# Sheet1.net
KiCad netlist of a schematic drawn in Altium Designer
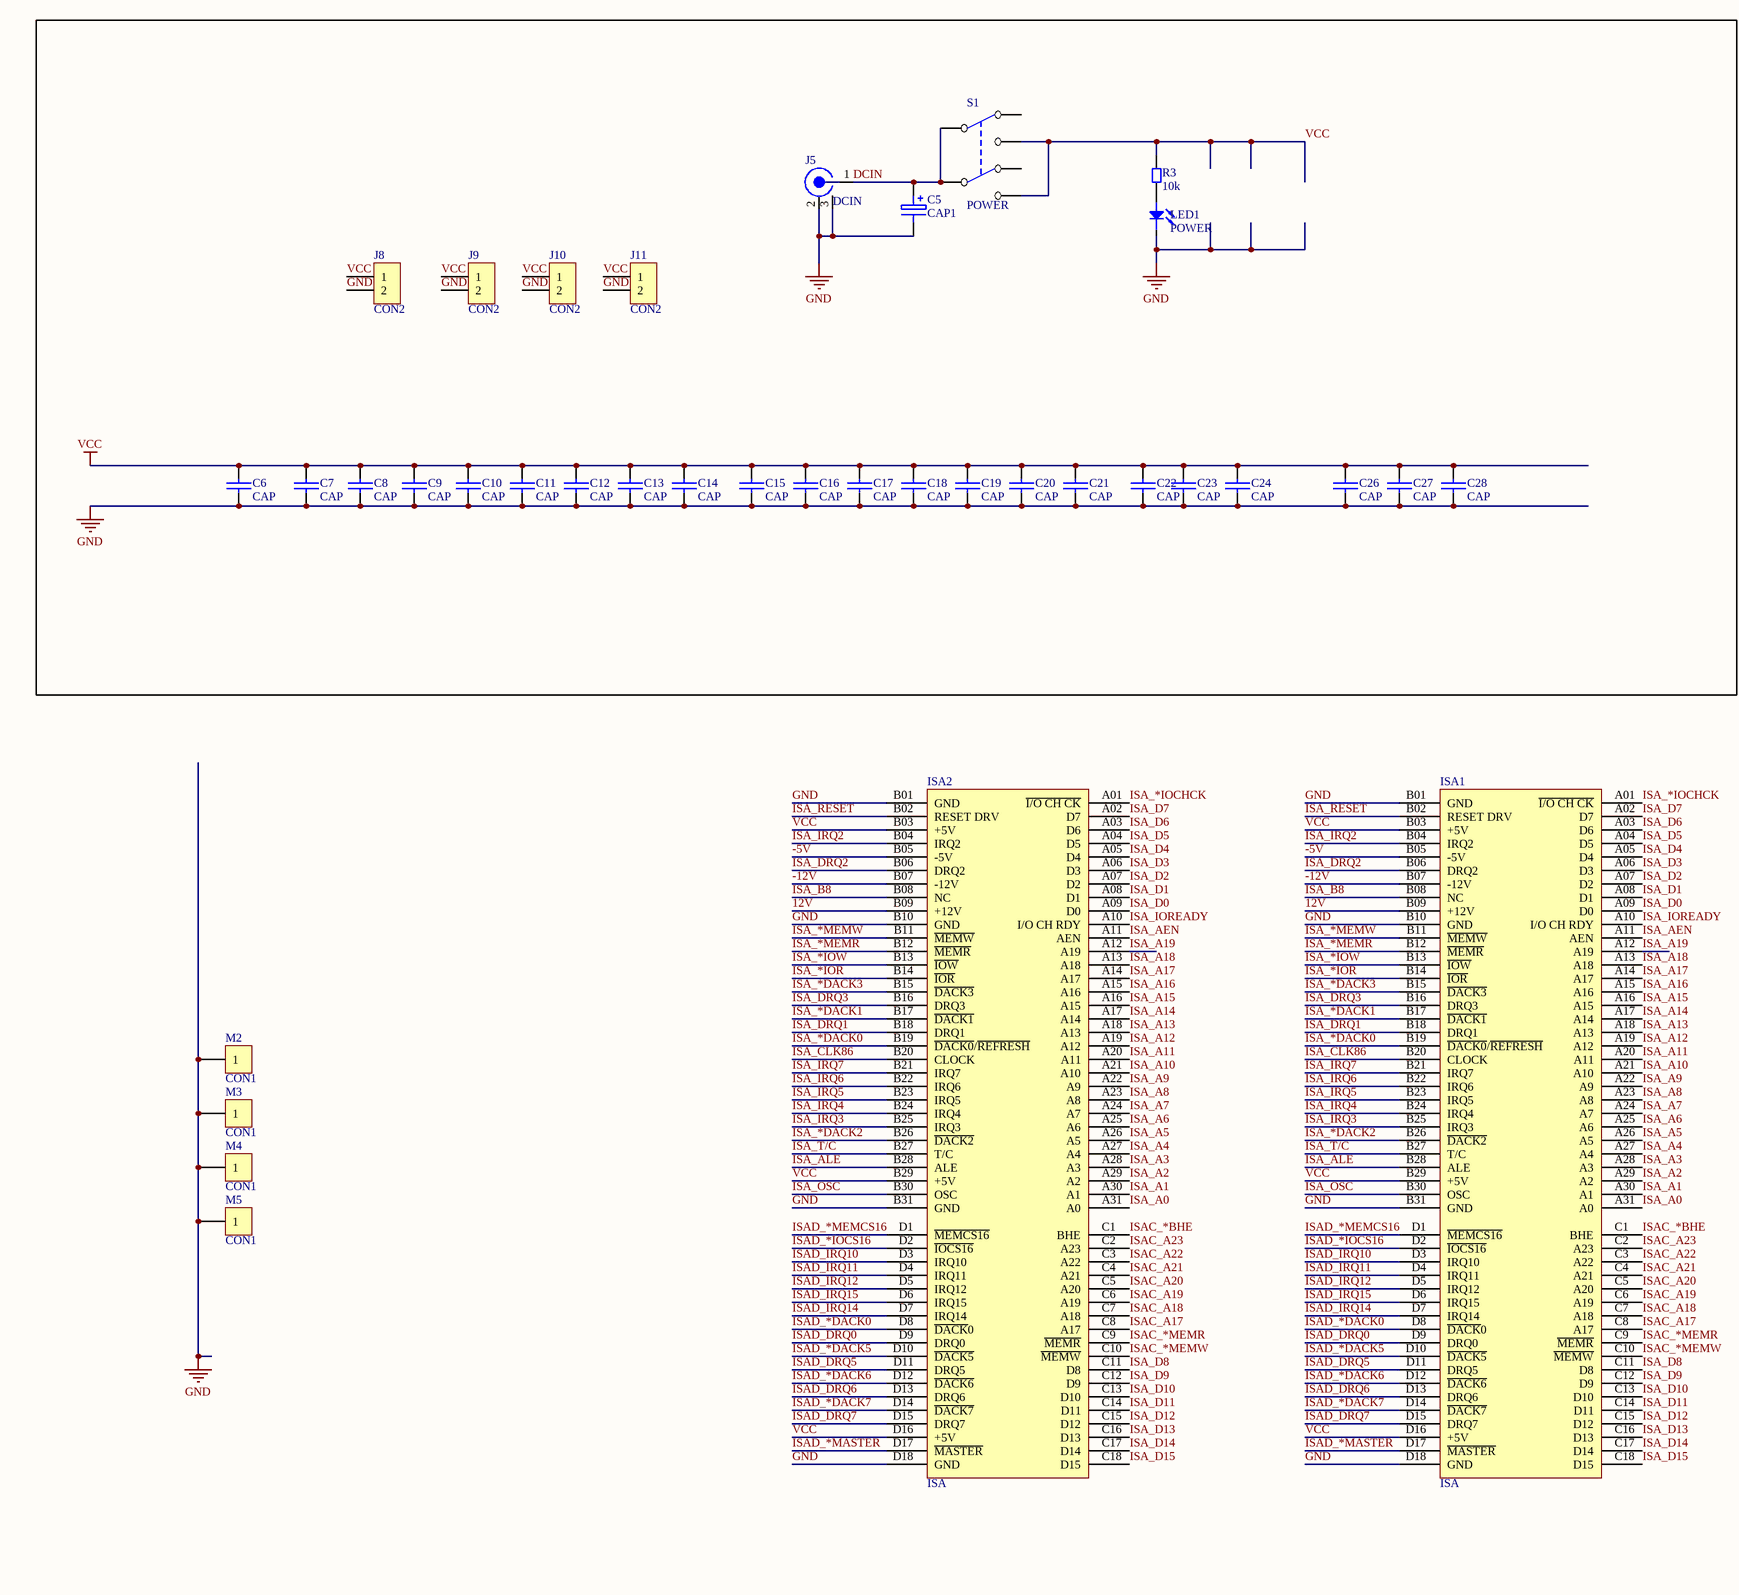
[diagram p0: Sheet1.SchDoc, left]
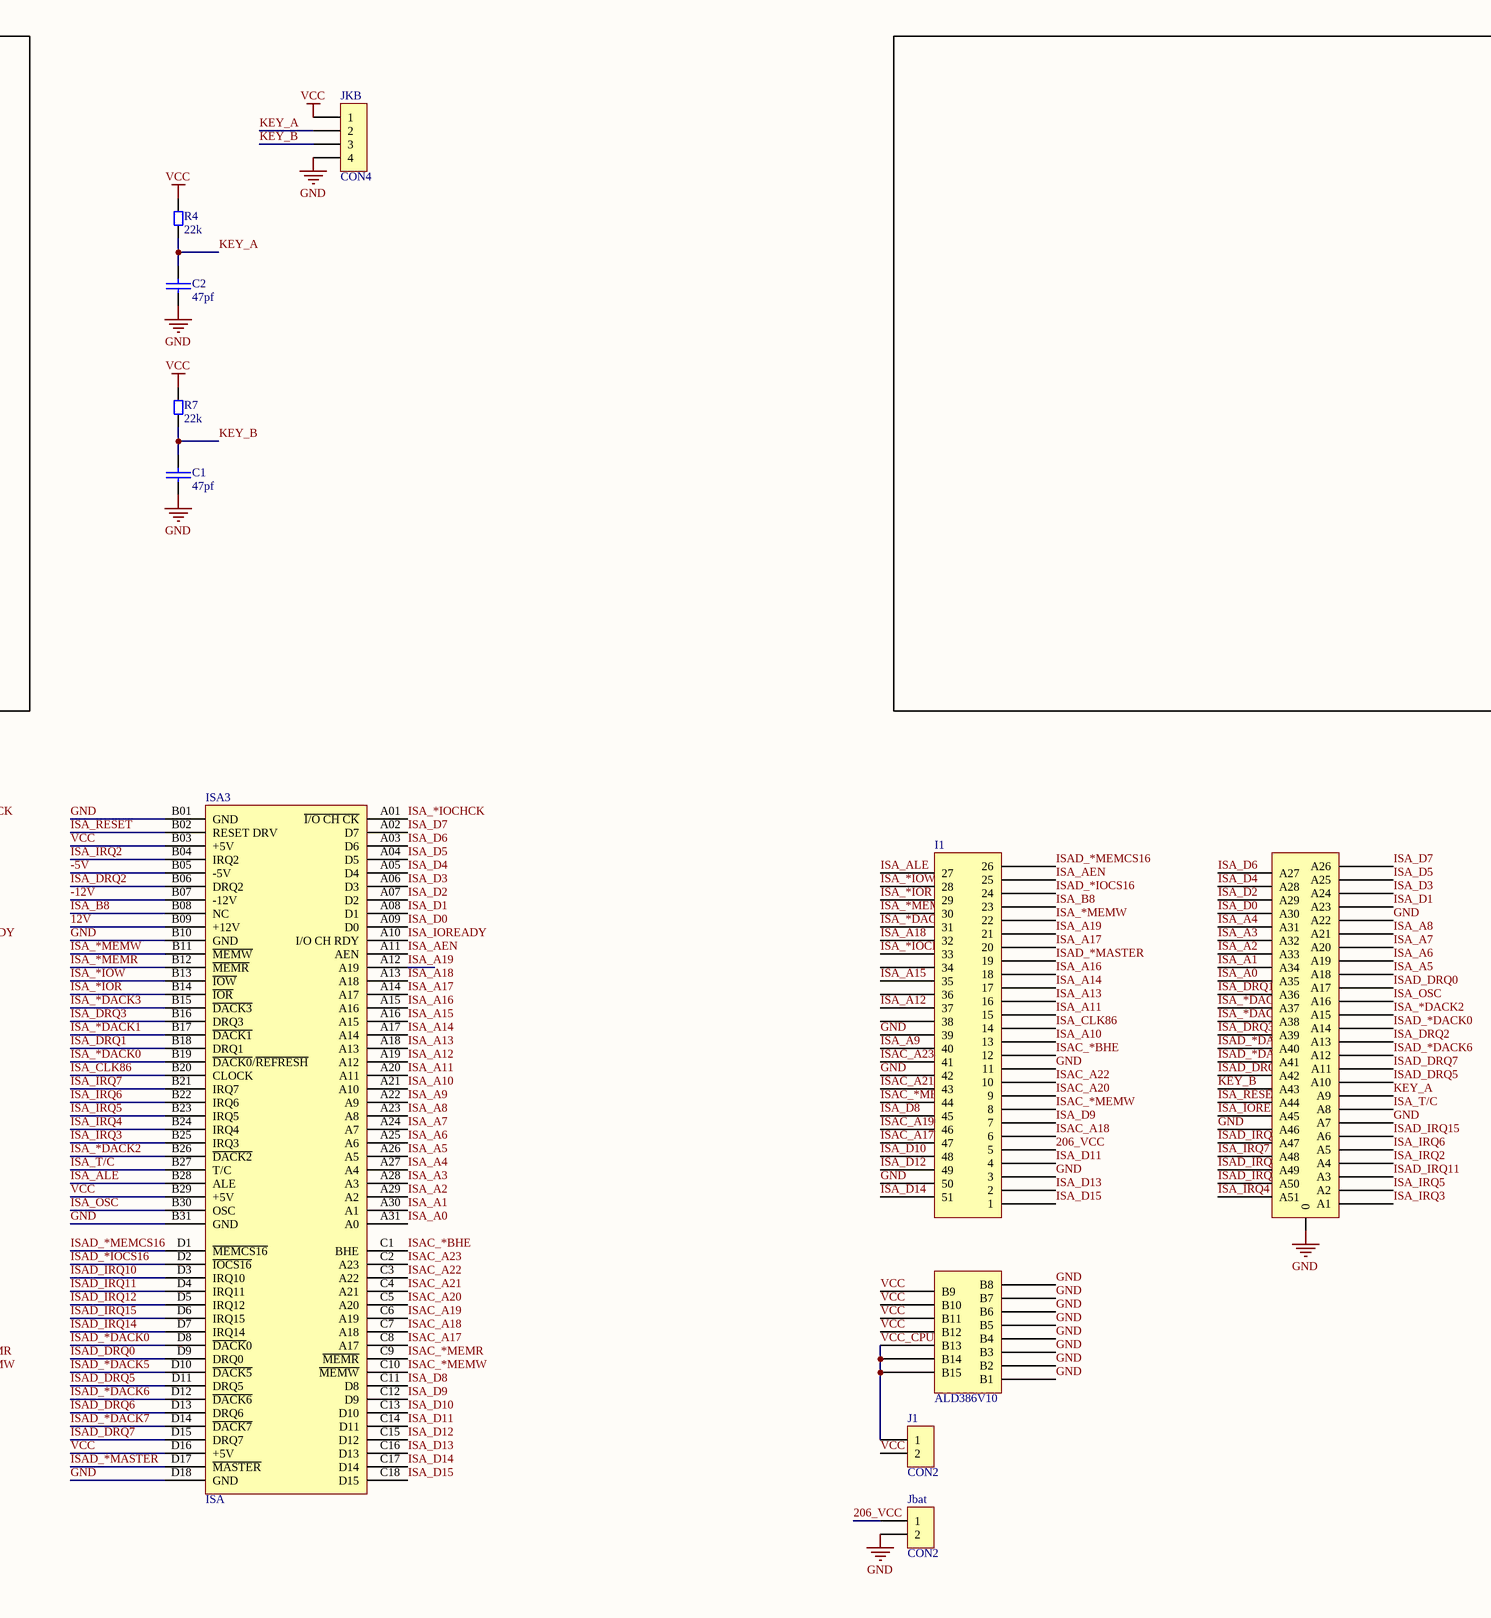
[diagram p1: Sheet1.SchDoc, middle]

(export (version "E")
  (design (tool "Eeschema 10.0.6"))
  (components
    (comp (ref "C1") (value "47pf") (footprint "C0603") (libsource (lib "电阻电容二极管") (part "CAP")))
    (comp (ref "C2") (value "47pf") (footprint "C0603") (libsource (lib "电阻电容二极管") (part "CAP")))
    (comp (ref "C5") (value "CAP1") (footprint "RB.2/.4") (libsource (lib "电阻电容二极管") (part "CAP1")))
    (comp (ref "C6") (value "CAP") (footprint "C0603") (libsource (lib "电阻电容二极管") (part "CAP")))
    (comp (ref "C7") (value "CAP") (footprint "C0603") (libsource (lib "电阻电容二极管") (part "CAP")))
    (comp (ref "C8") (value "CAP") (footprint "C0603") (libsource (lib "电阻电容二极管") (part "CAP")))
    (comp (ref "C9") (value "CAP") (footprint "C0603") (libsource (lib "电阻电容二极管") (part "CAP")))
    (comp (ref "C10") (value "CAP") (footprint "C0603") (libsource (lib "电阻电容二极管") (part "CAP")))
    (comp (ref "C11") (value "CAP") (footprint "C0603") (libsource (lib "电阻电容二极管") (part "CAP")))
    (comp (ref "C12") (value "CAP") (footprint "C0603") (libsource (lib "电阻电容二极管") (part "CAP")))
    (comp (ref "C13") (value "CAP") (footprint "C0603") (libsource (lib "电阻电容二极管") (part "CAP")))
    (comp (ref "C14") (value "CAP") (footprint "C0603") (libsource (lib "电阻电容二极管") (part "CAP")))
    (comp (ref "C15") (value "CAP") (footprint "C0603") (libsource (lib "电阻电容二极管") (part "CAP")))
    (comp (ref "C16") (value "CAP") (footprint "C0603") (libsource (lib "电阻电容二极管") (part "CAP")))
    (comp (ref "C17") (value "CAP") (footprint "C0603") (libsource (lib "电阻电容二极管") (part "CAP")))
    (comp (ref "C18") (value "CAP") (footprint "C0603") (libsource (lib "电阻电容二极管") (part "CAP")))
    (comp (ref "C19") (value "CAP") (footprint "C0603") (libsource (lib "电阻电容二极管") (part "CAP")))
    (comp (ref "C20") (value "CAP") (footprint "C0603") (libsource (lib "电阻电容二极管") (part "CAP")))
    (comp (ref "C21") (value "CAP") (footprint "C0603") (libsource (lib "电阻电容二极管") (part "CAP")))
    (comp (ref "C22") (value "CAP") (footprint "C0603") (libsource (lib "电阻电容二极管") (part "CAP")))
    (comp (ref "C23") (value "CAP") (footprint "C0603") (libsource (lib "电阻电容二极管") (part "CAP")))
    (comp (ref "C24") (value "CAP") (footprint "C0603") (libsource (lib "电阻电容二极管") (part "CAP")))
    (comp (ref "C26") (value "CAP") (footprint "C0603") (libsource (lib "电阻电容二极管") (part "CAP")))
    (comp (ref "C27") (value "CAP") (footprint "C0603") (libsource (lib "电阻电容二极管") (part "CAP")))
    (comp (ref "C28") (value "CAP") (footprint "C0603") (libsource (lib "电阻电容二极管") (part "CAP")))
    (comp (ref "I1")
      (value "ALD386V10")
      (footprint "MY-ALD386V10")
      (libsource (lib "微机原理") (part "ALD386V10"))
    )
    (comp (ref "ISA1") (value "ISA") (libsource (lib "微机原理") (part "ISA")))
    (comp (ref "ISA2") (value "ISA") (libsource (lib "微机原理") (part "ISA")))
    (comp (ref "ISA3") (value "ISA") (libsource (lib "微机原理") (part "ISA")))
    (comp (ref "J1") (value "CON2") (footprint "SIP2") (libsource (lib "常用元件库") (part "CON2")))
    (comp (ref "J5")
      (value "DCIN")
      (footprint "DC5.5-2.5")
      (description "Connector")
      (libsource (lib "插件") (part "DCIN"))
    )
    (comp (ref "J8") (value "CON2") (footprint "SIP2") (libsource (lib "常用元件库") (part "CON2")))
    (comp (ref "J9") (value "CON2") (footprint "SIP2") (libsource (lib "常用元件库") (part "CON2")))
    (comp (ref "J10") (value "CON2") (footprint "SIP2") (libsource (lib "常用元件库") (part "CON2")))
    (comp (ref "J11") (value "CON2") (footprint "SIP2") (libsource (lib "常用元件库") (part "CON2")))
    (comp (ref "Jbat") (value "CON2") (footprint "XH2.54-2") (libsource (lib "常用元件库") (part "CON2")))
    (comp (ref "JKB") (value "CON4") (footprint "XH2.54-4") (libsource (lib "常用元件库") (part "CON4")))
    (comp (ref "LED1") (value "POWER") (footprint "LED0603") (libsource (lib "电阻电容二极管") (part "LED")))
    (comp (ref "M2") (value "CON1") (footprint "M3") (libsource (lib "常用元件库") (part "CON1")))
    (comp (ref "M3") (value "CON1") (footprint "M3") (libsource (lib "常用元件库") (part "CON1")))
    (comp (ref "M4") (value "CON1") (footprint "M3") (libsource (lib "常用元件库") (part "CON1")))
    (comp (ref "M5") (value "CON1") (footprint "M3") (libsource (lib "常用元件库") (part "CON1")))
    (comp (ref "R3") (value "10k") (footprint "R0603") (libsource (lib "电阻电容二极管") (part "RES2")))
    (comp (ref "R4") (value "22k") (footprint "R0603") (libsource (lib "电阻电容二极管") (part "RES2")))
    (comp (ref "R7") (value "22k") (footprint "R0603") (libsource (lib "电阻电容二极管") (part "RES2")))
    (comp (ref "S1") (value "POWER") (footprint "SW 8x8") (libsource (lib "开关") (part "双刀双柄开关")))
  )
  (nets
    (net (code "1") (name "/-5V") (class "Default")
      (node (ref "ISA1") (pin "B05") (pinfunction "-5V_B05") (pintype "passive"))
      (node (ref "ISA2") (pin "B05") (pinfunction "-5V_B05") (pintype "passive"))
      (node (ref "ISA3") (pin "B05") (pinfunction "-5V_B05") (pintype "passive"))
    )
    (net (code "2") (name "/-12V") (class "Default")
      (node (ref "ISA1") (pin "B07") (pinfunction "-12V_B07") (pintype "passive"))
      (node (ref "ISA2") (pin "B07") (pinfunction "-12V_B07") (pintype "passive"))
      (node (ref "ISA3") (pin "B07") (pinfunction "-12V_B07") (pintype "passive"))
    )
    (net (code "3") (name "/12V") (class "Default")
      (node (ref "ISA1") (pin "B09") (pinfunction "+12V_B09") (pintype "passive"))
      (node (ref "ISA2") (pin "B09") (pinfunction "+12V_B09") (pintype "passive"))
      (node (ref "ISA3") (pin "B09") (pinfunction "+12V_B09") (pintype "passive"))
    )
    (net (code "4") (name "/206_VCC") (class "Default")
      (node (ref "I1") (pin "5") (pinfunction "5_5") (pintype "passive"))
      (node (ref "Jbat") (pin "1") (pinfunction "1_1") (pintype "passive"))
    )
    (net (code "5") (name "/DCIN") (class "Default")
      (node (ref "C5") (pin "1") (pinfunction "1_1") (pintype "passive"))
      (node (ref "J5") (pin "1") (pinfunction "+_1") (pintype "passive"))
      (node (ref "S1") (pin "3") (pinfunction "COMMON1_3") (pintype "passive"))
      (node (ref "S1") (pin "6") (pinfunction "NO2_6") (pintype "passive"))
    )
    (net (code "6") (name "/ISAC_*BHE") (class "Default")
      (node (ref "I1") (pin "12") (pinfunction "12_12") (pintype "passive"))
      (node (ref "ISA1") (pin "C1") (pinfunction "BHE_C1") (pintype "passive"))
      (node (ref "ISA2") (pin "C1") (pinfunction "BHE_C1") (pintype "passive"))
      (node (ref "ISA3") (pin "C1") (pinfunction "BHE_C1") (pintype "passive"))
    )
    (net (code "7") (name "/ISAC_*MEMR") (class "Default")
      (node (ref "I1") (pin "44") (pinfunction "44_44") (pintype "passive"))
      (node (ref "ISA1") (pin "C9") (pinfunction "~{MEMR}_C9") (pintype "passive"))
      (node (ref "ISA2") (pin "C9") (pinfunction "~{MEMR}_C9") (pintype "passive"))
      (node (ref "ISA3") (pin "C9") (pinfunction "~{MEMR}_C9") (pintype "passive"))
    )
    (net (code "8") (name "/ISAC_*MEMW") (class "Default")
      (node (ref "I1") (pin "8") (pinfunction "8_8") (pintype "passive"))
      (node (ref "ISA1") (pin "C10") (pinfunction "~{MEMW}_C10") (pintype "passive"))
      (node (ref "ISA2") (pin "C10") (pinfunction "~{MEMW}_C10") (pintype "passive"))
      (node (ref "ISA3") (pin "C10") (pinfunction "~{MEMW}_C10") (pintype "passive"))
    )
    (net (code "9") (name "/ISAC_A17") (class "Default")
      (node (ref "I1") (pin "47") (pinfunction "47_47") (pintype "passive"))
      (node (ref "ISA1") (pin "C8") (pinfunction "A17_C8") (pintype "passive"))
      (node (ref "ISA2") (pin "C8") (pinfunction "A17_C8") (pintype "passive"))
      (node (ref "ISA3") (pin "C8") (pinfunction "A17_C8") (pintype "passive"))
    )
    (net (code "10") (name "/ISAC_A18") (class "Default")
      (node (ref "I1") (pin "6") (pinfunction "6_6") (pintype "passive"))
      (node (ref "ISA1") (pin "C7") (pinfunction "A18_C7") (pintype "passive"))
      (node (ref "ISA2") (pin "C7") (pinfunction "A18_C7") (pintype "passive"))
      (node (ref "ISA3") (pin "C7") (pinfunction "A18_C7") (pintype "passive"))
    )
    (net (code "11") (name "/ISAC_A19") (class "Default")
      (node (ref "I1") (pin "46") (pinfunction "46_46") (pintype "passive"))
      (node (ref "ISA1") (pin "C6") (pinfunction "A19_C6") (pintype "passive"))
      (node (ref "ISA2") (pin "C6") (pinfunction "A19_C6") (pintype "passive"))
      (node (ref "ISA3") (pin "C6") (pinfunction "A19_C6") (pintype "passive"))
    )
    (net (code "12") (name "/ISAC_A20") (class "Default")
      (node (ref "I1") (pin "9") (pinfunction "9_9") (pintype "passive"))
      (node (ref "ISA1") (pin "C5") (pinfunction "A20_C5") (pintype "passive"))
      (node (ref "ISA2") (pin "C5") (pinfunction "A20_C5") (pintype "passive"))
      (node (ref "ISA3") (pin "C5") (pinfunction "A20_C5") (pintype "passive"))
    )
    (net (code "13") (name "/ISAC_A21") (class "Default")
      (node (ref "I1") (pin "43") (pinfunction "43_43") (pintype "passive"))
      (node (ref "ISA1") (pin "C4") (pinfunction "A21_C4") (pintype "passive"))
      (node (ref "ISA2") (pin "C4") (pinfunction "A21_C4") (pintype "passive"))
      (node (ref "ISA3") (pin "C4") (pinfunction "A21_C4") (pintype "passive"))
    )
    (net (code "14") (name "/ISAC_A22") (class "Default")
      (node (ref "I1") (pin "10") (pinfunction "10_10") (pintype "passive"))
      (node (ref "ISA1") (pin "C3") (pinfunction "A22_C3") (pintype "passive"))
      (node (ref "ISA2") (pin "C3") (pinfunction "A22_C3") (pintype "passive"))
      (node (ref "ISA3") (pin "C3") (pinfunction "A22_C3") (pintype "passive"))
    )
    (net (code "15") (name "/ISAC_A23") (class "Default")
      (node (ref "I1") (pin "41") (pinfunction "41_41") (pintype "passive"))
      (node (ref "ISA1") (pin "C2") (pinfunction "A23_C2") (pintype "passive"))
      (node (ref "ISA2") (pin "C2") (pinfunction "A23_C2") (pintype "passive"))
      (node (ref "ISA3") (pin "C2") (pinfunction "A23_C2") (pintype "passive"))
    )
    (net (code "16") (name "/ISAD_*DACK0") (class "Default")
      (node (ref "I1") (pin "A14") (pinfunction "A14_A14") (pintype "passive"))
      (node (ref "ISA1") (pin "D8") (pinfunction "~{DACK}0_D8") (pintype "passive"))
      (node (ref "ISA2") (pin "D8") (pinfunction "~{DACK}0_D8") (pintype "passive"))
      (node (ref "ISA3") (pin "D8") (pinfunction "~{DACK}0_D8") (pintype "passive"))
    )
    (net (code "17") (name "/ISAD_*DACK5") (class "Default")
      (node (ref "I1") (pin "A41") (pinfunction "A41_A41") (pintype "passive"))
      (node (ref "ISA1") (pin "D10") (pinfunction "~{DACK5}_D10") (pintype "passive"))
      (node (ref "ISA2") (pin "D10") (pinfunction "~{DACK5}_D10") (pintype "passive"))
      (node (ref "ISA3") (pin "D10") (pinfunction "~{DACK5}_D10") (pintype "passive"))
    )
    (net (code "18") (name "/ISAD_*DACK6") (class "Default")
      (node (ref "I1") (pin "A12") (pinfunction "A12_A12") (pintype "passive"))
      (node (ref "ISA1") (pin "D12") (pinfunction "~{DACK6}_D12") (pintype "passive"))
      (node (ref "ISA2") (pin "D12") (pinfunction "~{DACK6}_D12") (pintype "passive"))
      (node (ref "ISA3") (pin "D12") (pinfunction "~{DACK6}_D12") (pintype "passive"))
    )
    (net (code "19") (name "/ISAD_*DACK7") (class "Default")
      (node (ref "I1") (pin "A40") (pinfunction "A40_A40") (pintype "passive"))
      (node (ref "ISA1") (pin "D14") (pinfunction "~{DACK7}_D14") (pintype "passive"))
      (node (ref "ISA2") (pin "D14") (pinfunction "~{DACK7}_D14") (pintype "passive"))
      (node (ref "ISA3") (pin "D14") (pinfunction "~{DACK7}_D14") (pintype "passive"))
    )
    (net (code "20") (name "/ISAD_*IOCS16") (class "Default")
      (node (ref "I1") (pin "24") (pinfunction "24_24") (pintype "passive"))
      (node (ref "ISA1") (pin "D2") (pinfunction "~{IOCS16}_D2") (pintype "passive"))
      (node (ref "ISA2") (pin "D2") (pinfunction "~{IOCS16}_D2") (pintype "passive"))
      (node (ref "ISA3") (pin "D2") (pinfunction "~{IOCS16}_D2") (pintype "passive"))
    )
    (net (code "21") (name "/ISAD_*MASTER") (class "Default")
      (node (ref "I1") (pin "19") (pinfunction "19_19") (pintype "passive"))
      (node (ref "ISA1") (pin "D17") (pinfunction "~{MASTER}_D17") (pintype "passive"))
      (node (ref "ISA2") (pin "D17") (pinfunction "~{MASTER}_D17") (pintype "passive"))
      (node (ref "ISA3") (pin "D17") (pinfunction "~{MASTER}_D17") (pintype "passive"))
    )
    (net (code "22") (name "/ISAD_*MEMCS16") (class "Default")
      (node (ref "I1") (pin "26") (pinfunction "26_26") (pintype "passive"))
      (node (ref "ISA1") (pin "D1") (pinfunction "~{MEMCS16}_D1") (pintype "passive"))
      (node (ref "ISA2") (pin "D1") (pinfunction "~{MEMCS16}_D1") (pintype "passive"))
      (node (ref "ISA3") (pin "D1") (pinfunction "~{MEMCS16}_D1") (pintype "passive"))
    )
    (net (code "23") (name "/ISAD_DRQ0") (class "Default")
      (node (ref "I1") (pin "A17") (pinfunction "A17_A17") (pintype "passive"))
      (node (ref "ISA1") (pin "D9") (pinfunction "DRQ0_D9") (pintype "passive"))
      (node (ref "ISA2") (pin "D9") (pinfunction "DRQ0_D9") (pintype "passive"))
      (node (ref "ISA3") (pin "D9") (pinfunction "DRQ0_D9") (pintype "passive"))
    )
    (net (code "24") (name "/ISAD_DRQ5") (class "Default")
      (node (ref "I1") (pin "A10") (pinfunction "A10_A10") (pintype "passive"))
      (node (ref "ISA1") (pin "D11") (pinfunction "DRQ5_D11") (pintype "passive"))
      (node (ref "ISA2") (pin "D11") (pinfunction "DRQ5_D11") (pintype "passive"))
      (node (ref "ISA3") (pin "D11") (pinfunction "DRQ5_D11") (pintype "passive"))
    )
    (net (code "25") (name "/ISAD_DRQ6") (class "Default")
      (node (ref "I1") (pin "A42") (pinfunction "A42_A42") (pintype "passive"))
      (node (ref "ISA1") (pin "D13") (pinfunction "DRQ6_D13") (pintype "passive"))
      (node (ref "ISA2") (pin "D13") (pinfunction "DRQ6_D13") (pintype "passive"))
      (node (ref "ISA3") (pin "D13") (pinfunction "DRQ6_D13") (pintype "passive"))
    )
    (net (code "26") (name "/ISAD_DRQ7") (class "Default")
      (node (ref "I1") (pin "A11") (pinfunction "A11_A11") (pintype "passive"))
      (node (ref "ISA1") (pin "D15") (pinfunction "DRQ7_D15") (pintype "passive"))
      (node (ref "ISA2") (pin "D15") (pinfunction "DRQ7_D15") (pintype "passive"))
      (node (ref "ISA3") (pin "D15") (pinfunction "DRQ7_D15") (pintype "passive"))
    )
    (net (code "27") (name "/ISAD_IRQ10") (class "Default")
      (node (ref "I1") (pin "A49") (pinfunction "A49_A49") (pintype "passive"))
      (node (ref "ISA1") (pin "D3") (pinfunction "IRQ10_D3") (pintype "passive"))
      (node (ref "ISA2") (pin "D3") (pinfunction "IRQ10_D3") (pintype "passive"))
      (node (ref "ISA3") (pin "D3") (pinfunction "IRQ10_D3") (pintype "passive"))
    )
    (net (code "28") (name "/ISAD_IRQ11") (class "Default")
      (node (ref "I1") (pin "A3") (pinfunction "A3_A3") (pintype "passive"))
      (node (ref "ISA1") (pin "D4") (pinfunction "IRQ11_D4") (pintype "passive"))
      (node (ref "ISA2") (pin "D4") (pinfunction "IRQ11_D4") (pintype "passive"))
      (node (ref "ISA3") (pin "D4") (pinfunction "IRQ11_D4") (pintype "passive"))
    )
    (net (code "29") (name "/ISAD_IRQ12") (class "Default")
      (node (ref "I1") (pin "A50") (pinfunction "A50_A50") (pintype "passive"))
      (node (ref "ISA1") (pin "D5") (pinfunction "IRQ12_D5") (pintype "passive"))
      (node (ref "ISA2") (pin "D5") (pinfunction "IRQ12_D5") (pintype "passive"))
      (node (ref "ISA3") (pin "D5") (pinfunction "IRQ12_D5") (pintype "passive"))
    )
    (net (code "30") (name "/ISAD_IRQ14") (class "Default")
      (node (ref "I1") (pin "A47") (pinfunction "A47_A47") (pintype "passive"))
      (node (ref "ISA1") (pin "D7") (pinfunction "IRQ14_D7") (pintype "passive"))
      (node (ref "ISA2") (pin "D7") (pinfunction "IRQ14_D7") (pintype "passive"))
      (node (ref "ISA3") (pin "D7") (pinfunction "IRQ14_D7") (pintype "passive"))
    )
    (net (code "31") (name "/ISAD_IRQ15") (class "Default")
      (node (ref "I1") (pin "A6") (pinfunction "A6_A6") (pintype "passive"))
      (node (ref "ISA1") (pin "D6") (pinfunction "IRQ15_D6") (pintype "passive"))
      (node (ref "ISA2") (pin "D6") (pinfunction "IRQ15_D6") (pintype "passive"))
      (node (ref "ISA3") (pin "D6") (pinfunction "IRQ15_D6") (pintype "passive"))
    )
    (net (code "32") (name "/ISA_*DACK0") (class "Default")
      (node (ref "I1") (pin "31") (pinfunction "31_31") (pintype "passive"))
      (node (ref "ISA1") (pin "B19") (pinfunction "~{DACK0}/~{REFRESH}_B19") (pintype "passive"))
      (node (ref "ISA2") (pin "B19") (pinfunction "~{DACK0}/~{REFRESH}_B19") (pintype "passive"))
      (node (ref "ISA3") (pin "B19") (pinfunction "~{DACK0}/~{REFRESH}_B19") (pintype "passive"))
    )
    (net (code "33") (name "/ISA_*DACK1") (class "Default")
      (node (ref "I1") (pin "A38") (pinfunction "A38_A38") (pintype "passive"))
      (node (ref "ISA1") (pin "B17") (pinfunction "~{DACK1}_B17") (pintype "passive"))
      (node (ref "ISA2") (pin "B17") (pinfunction "~{DACK1}_B17") (pintype "passive"))
      (node (ref "ISA3") (pin "B17") (pinfunction "~{DACK1}_B17") (pintype "passive"))
    )
    (net (code "34") (name "/ISA_*DACK2") (class "Default")
      (node (ref "I1") (pin "A15") (pinfunction "A15_A15") (pintype "passive"))
      (node (ref "ISA1") (pin "B26") (pinfunction "~{DACK2}_B26") (pintype "passive"))
      (node (ref "ISA2") (pin "B26") (pinfunction "~{DACK2}_B26") (pintype "passive"))
      (node (ref "ISA3") (pin "B26") (pinfunction "~{DACK2}_B26") (pintype "passive"))
    )
    (net (code "35") (name "/ISA_*DACK3") (class "Default")
      (node (ref "I1") (pin "A37") (pinfunction "A37_A37") (pintype "passive"))
      (node (ref "ISA1") (pin "B15") (pinfunction "~{DACK3}_B15") (pintype "passive"))
      (node (ref "ISA2") (pin "B15") (pinfunction "~{DACK3}_B15") (pintype "passive"))
      (node (ref "ISA3") (pin "B15") (pinfunction "~{DACK3}_B15") (pintype "passive"))
    )
    (net (code "36") (name "/ISA_*IOCHCK") (class "Default")
      (node (ref "I1") (pin "33") (pinfunction "33_33") (pintype "passive"))
      (node (ref "ISA1") (pin "A01") (pinfunction "~{I/O_CH_CK}_A01") (pintype "passive"))
      (node (ref "ISA2") (pin "A01") (pinfunction "~{I/O_CH_CK}_A01") (pintype "passive"))
      (node (ref "ISA3") (pin "A01") (pinfunction "~{I/O_CH_CK}_A01") (pintype "passive"))
    )
    (net (code "37") (name "/ISA_*IOR") (class "Default")
      (node (ref "I1") (pin "29") (pinfunction "29_29") (pintype "passive"))
      (node (ref "ISA1") (pin "B14") (pinfunction "~{IOR}_B14") (pintype "passive"))
      (node (ref "ISA2") (pin "B14") (pinfunction "~{IOR}_B14") (pintype "passive"))
      (node (ref "ISA3") (pin "B14") (pinfunction "~{IOR}_B14") (pintype "passive"))
    )
    (net (code "38") (name "/ISA_*IOW") (class "Default")
      (node (ref "I1") (pin "28") (pinfunction "28_28") (pintype "passive"))
      (node (ref "ISA1") (pin "B13") (pinfunction "~{IOW}_B13") (pintype "passive"))
      (node (ref "ISA2") (pin "B13") (pinfunction "~{IOW}_B13") (pintype "passive"))
      (node (ref "ISA3") (pin "B13") (pinfunction "~{IOW}_B13") (pintype "passive"))
    )
    (net (code "39") (name "/ISA_*MEMR") (class "Default")
      (node (ref "I1") (pin "30") (pinfunction "30_30") (pintype "passive"))
      (node (ref "ISA1") (pin "B12") (pinfunction "~{MEMR}_B12") (pintype "passive"))
      (node (ref "ISA2") (pin "B12") (pinfunction "~{MEMR}_B12") (pintype "passive"))
      (node (ref "ISA3") (pin "B12") (pinfunction "~{MEMR}_B12") (pintype "passive"))
    )
    (net (code "40") (name "/ISA_*MEMW") (class "Default")
      (node (ref "I1") (pin "22") (pinfunction "22_22") (pintype "passive"))
      (node (ref "ISA1") (pin "B11") (pinfunction "~{MEMW}_B11") (pintype "passive"))
      (node (ref "ISA2") (pin "B11") (pinfunction "~{MEMW}_B11") (pintype "passive"))
      (node (ref "ISA3") (pin "B11") (pinfunction "~{MEMW}_B11") (pintype "passive"))
    )
    (net (code "41") (name "/ISA_A0") (class "Default")
      (node (ref "I1") (pin "A35") (pinfunction "A35_A35") (pintype "passive"))
      (node (ref "ISA1") (pin "A31") (pinfunction "A0_A31") (pintype "passive"))
      (node (ref "ISA2") (pin "A31") (pinfunction "A0_A31") (pintype "passive"))
      (node (ref "ISA3") (pin "A31") (pinfunction "A0_A31") (pintype "passive"))
    )
    (net (code "42") (name "/ISA_A1") (class "Default")
      (node (ref "I1") (pin "A34") (pinfunction "A34_A34") (pintype "passive"))
      (node (ref "ISA1") (pin "A30") (pinfunction "A1_A30") (pintype "passive"))
      (node (ref "ISA2") (pin "A30") (pinfunction "A1_A30") (pintype "passive"))
      (node (ref "ISA3") (pin "A30") (pinfunction "A1_A30") (pintype "passive"))
    )
    (net (code "43") (name "/ISA_A2") (class "Default")
      (node (ref "I1") (pin "A33") (pinfunction "A33_A33") (pintype "passive"))
      (node (ref "ISA1") (pin "A29") (pinfunction "A2_A29") (pintype "passive"))
      (node (ref "ISA2") (pin "A29") (pinfunction "A2_A29") (pintype "passive"))
      (node (ref "ISA3") (pin "A29") (pinfunction "A2_A29") (pintype "passive"))
    )
    (net (code "44") (name "/ISA_A3") (class "Default")
      (node (ref "I1") (pin "A32") (pinfunction "A32_A32") (pintype "passive"))
      (node (ref "ISA1") (pin "A28") (pinfunction "A3_A28") (pintype "passive"))
      (node (ref "ISA2") (pin "A28") (pinfunction "A3_A28") (pintype "passive"))
      (node (ref "ISA3") (pin "A28") (pinfunction "A3_A28") (pintype "passive"))
    )
    (net (code "45") (name "/ISA_A4") (class "Default")
      (node (ref "I1") (pin "A31") (pinfunction "A31_A31") (pintype "passive"))
      (node (ref "ISA1") (pin "A27") (pinfunction "A4_A27") (pintype "passive"))
      (node (ref "ISA2") (pin "A27") (pinfunction "A4_A27") (pintype "passive"))
      (node (ref "ISA3") (pin "A27") (pinfunction "A4_A27") (pintype "passive"))
    )
    (net (code "46") (name "/ISA_A5") (class "Default")
      (node (ref "I1") (pin "A18") (pinfunction "A18_A18") (pintype "passive"))
      (node (ref "ISA1") (pin "A26") (pinfunction "A5_A26") (pintype "passive"))
      (node (ref "ISA2") (pin "A26") (pinfunction "A5_A26") (pintype "passive"))
      (node (ref "ISA3") (pin "A26") (pinfunction "A5_A26") (pintype "passive"))
    )
    (net (code "47") (name "/ISA_A6") (class "Default")
      (node (ref "I1") (pin "A19") (pinfunction "A19_A19") (pintype "passive"))
      (node (ref "ISA1") (pin "A25") (pinfunction "A6_A25") (pintype "passive"))
      (node (ref "ISA2") (pin "A25") (pinfunction "A6_A25") (pintype "passive"))
      (node (ref "ISA3") (pin "A25") (pinfunction "A6_A25") (pintype "passive"))
    )
    (net (code "48") (name "/ISA_A7") (class "Default")
      (node (ref "I1") (pin "A20") (pinfunction "A20_A20") (pintype "passive"))
      (node (ref "ISA1") (pin "A24") (pinfunction "A7_A24") (pintype "passive"))
      (node (ref "ISA2") (pin "A24") (pinfunction "A7_A24") (pintype "passive"))
      (node (ref "ISA3") (pin "A24") (pinfunction "A7_A24") (pintype "passive"))
    )
    (net (code "49") (name "/ISA_A8") (class "Default")
      (node (ref "I1") (pin "A21") (pinfunction "A21_A21") (pintype "passive"))
      (node (ref "ISA1") (pin "A23") (pinfunction "A8_A23") (pintype "passive"))
      (node (ref "ISA2") (pin "A23") (pinfunction "A8_A23") (pintype "passive"))
      (node (ref "ISA3") (pin "A23") (pinfunction "A8_A23") (pintype "passive"))
    )
    (net (code "50") (name "/ISA_A9") (class "Default")
      (node (ref "I1") (pin "40") (pinfunction "40_40") (pintype "passive"))
      (node (ref "ISA1") (pin "A22") (pinfunction "A9_A22") (pintype "passive"))
      (node (ref "ISA2") (pin "A22") (pinfunction "A9_A22") (pintype "passive"))
      (node (ref "ISA3") (pin "A22") (pinfunction "A9_A22") (pintype "passive"))
    )
    (net (code "51") (name "/ISA_A10") (class "Default")
      (node (ref "I1") (pin "13") (pinfunction "13_13") (pintype "passive"))
      (node (ref "ISA1") (pin "A21") (pinfunction "A10_A21") (pintype "passive"))
      (node (ref "ISA2") (pin "A21") (pinfunction "A10_A21") (pintype "passive"))
      (node (ref "ISA3") (pin "A21") (pinfunction "A10_A21") (pintype "passive"))
    )
    (net (code "52") (name "/ISA_A11") (class "Default")
      (node (ref "I1") (pin "15") (pinfunction "15_15") (pintype "passive"))
      (node (ref "ISA1") (pin "A20") (pinfunction "A11_A20") (pintype "passive"))
      (node (ref "ISA2") (pin "A20") (pinfunction "A11_A20") (pintype "passive"))
      (node (ref "ISA3") (pin "A20") (pinfunction "A11_A20") (pintype "passive"))
    )
    (net (code "53") (name "/ISA_A12") (class "Default")
      (node (ref "I1") (pin "37") (pinfunction "37_37") (pintype "passive"))
      (node (ref "ISA1") (pin "A19") (pinfunction "A12_A19") (pintype "passive"))
      (node (ref "ISA2") (pin "A19") (pinfunction "A12_A19") (pintype "passive"))
      (node (ref "ISA3") (pin "A19") (pinfunction "A12_A19") (pintype "passive"))
    )
    (net (code "54") (name "/ISA_A13") (class "Default")
      (node (ref "I1") (pin "16") (pinfunction "16_16") (pintype "passive"))
      (node (ref "ISA1") (pin "A18") (pinfunction "A13_A18") (pintype "passive"))
      (node (ref "ISA2") (pin "A18") (pinfunction "A13_A18") (pintype "passive"))
      (node (ref "ISA3") (pin "A18") (pinfunction "A13_A18") (pintype "passive"))
    )
    (net (code "55") (name "/ISA_A14") (class "Default")
      (node (ref "I1") (pin "17") (pinfunction "17_17") (pintype "passive"))
      (node (ref "ISA1") (pin "A17") (pinfunction "A14_A17") (pintype "passive"))
      (node (ref "ISA2") (pin "A17") (pinfunction "A14_A17") (pintype "passive"))
      (node (ref "ISA3") (pin "A17") (pinfunction "A14_A17") (pintype "passive"))
    )
    (net (code "56") (name "/ISA_A15") (class "Default")
      (node (ref "I1") (pin "35") (pinfunction "35_35") (pintype "passive"))
      (node (ref "ISA1") (pin "A16") (pinfunction "A15_A16") (pintype "passive"))
      (node (ref "ISA2") (pin "A16") (pinfunction "A15_A16") (pintype "passive"))
      (node (ref "ISA3") (pin "A16") (pinfunction "A15_A16") (pintype "passive"))
    )
    (net (code "57") (name "/ISA_A16") (class "Default")
      (node (ref "I1") (pin "18") (pinfunction "18_18") (pintype "passive"))
      (node (ref "ISA1") (pin "A15") (pinfunction "A16_A15") (pintype "passive"))
      (node (ref "ISA2") (pin "A15") (pinfunction "A16_A15") (pintype "passive"))
      (node (ref "ISA3") (pin "A15") (pinfunction "A16_A15") (pintype "passive"))
    )
    (net (code "58") (name "/ISA_A17") (class "Default")
      (node (ref "I1") (pin "20") (pinfunction "20_20") (pintype "passive"))
      (node (ref "ISA1") (pin "A14") (pinfunction "A17_A14") (pintype "passive"))
      (node (ref "ISA2") (pin "A14") (pinfunction "A17_A14") (pintype "passive"))
      (node (ref "ISA3") (pin "A14") (pinfunction "A17_A14") (pintype "passive"))
    )
    (net (code "59") (name "/ISA_A18") (class "Default")
      (node (ref "I1") (pin "32") (pinfunction "32_32") (pintype "passive"))
      (node (ref "ISA1") (pin "A13") (pinfunction "A18_A13") (pintype "passive"))
      (node (ref "ISA2") (pin "A13") (pinfunction "A18_A13") (pintype "passive"))
      (node (ref "ISA3") (pin "A13") (pinfunction "A18_A13") (pintype "passive"))
    )
    (net (code "60") (name "/ISA_A19") (class "Default")
      (node (ref "I1") (pin "21") (pinfunction "21_21") (pintype "passive"))
      (node (ref "ISA1") (pin "A12") (pinfunction "A19_A12") (pintype "passive"))
      (node (ref "ISA2") (pin "A12") (pinfunction "A19_A12") (pintype "passive"))
      (node (ref "ISA3") (pin "A12") (pinfunction "A19_A12") (pintype "passive"))
    )
    (net (code "61") (name "/ISA_AEN") (class "Default")
      (node (ref "I1") (pin "25") (pinfunction "25_25") (pintype "passive"))
      (node (ref "ISA1") (pin "A11") (pinfunction "AEN_A11") (pintype "passive"))
      (node (ref "ISA2") (pin "A11") (pinfunction "AEN_A11") (pintype "passive"))
      (node (ref "ISA3") (pin "A11") (pinfunction "AEN_A11") (pintype "passive"))
    )
    (net (code "62") (name "/ISA_ALE") (class "Default")
      (node (ref "I1") (pin "27") (pinfunction "27_27") (pintype "passive"))
      (node (ref "ISA1") (pin "B28") (pinfunction "ALE_B28") (pintype "passive"))
      (node (ref "ISA2") (pin "B28") (pinfunction "ALE_B28") (pintype "passive"))
      (node (ref "ISA3") (pin "B28") (pinfunction "ALE_B28") (pintype "passive"))
    )
    (net (code "63") (name "/ISA_B8") (class "Default")
      (node (ref "I1") (pin "23") (pinfunction "23_23") (pintype "passive"))
      (node (ref "ISA1") (pin "B08") (pinfunction "NC_B08") (pintype "passive"))
      (node (ref "ISA2") (pin "B08") (pinfunction "NC_B08") (pintype "passive"))
      (node (ref "ISA3") (pin "B08") (pinfunction "NC_B08") (pintype "passive"))
    )
    (net (code "64") (name "/ISA_CLK86") (class "Default")
      (node (ref "I1") (pin "14") (pinfunction "14_14") (pintype "passive"))
      (node (ref "ISA1") (pin "B20") (pinfunction "CLOCK_B20") (pintype "passive"))
      (node (ref "ISA2") (pin "B20") (pinfunction "CLOCK_B20") (pintype "passive"))
      (node (ref "ISA3") (pin "B20") (pinfunction "CLOCK_B20") (pintype "passive"))
    )
    (net (code "65") (name "/ISA_D0") (class "Default")
      (node (ref "I1") (pin "A30") (pinfunction "A30_A30") (pintype "passive"))
      (node (ref "ISA1") (pin "A09") (pinfunction "D0_A09") (pintype "passive"))
      (node (ref "ISA2") (pin "A09") (pinfunction "D0_A09") (pintype "passive"))
      (node (ref "ISA3") (pin "A09") (pinfunction "D0_A09") (pintype "passive"))
    )
    (net (code "66") (name "/ISA_D1") (class "Default")
      (node (ref "I1") (pin "A23") (pinfunction "A23_A23") (pintype "passive"))
      (node (ref "ISA1") (pin "A08") (pinfunction "D1_A08") (pintype "passive"))
      (node (ref "ISA2") (pin "A08") (pinfunction "D1_A08") (pintype "passive"))
      (node (ref "ISA3") (pin "A08") (pinfunction "D1_A08") (pintype "passive"))
    )
    (net (code "67") (name "/ISA_D2") (class "Default")
      (node (ref "I1") (pin "A29") (pinfunction "A29_A29") (pintype "passive"))
      (node (ref "ISA1") (pin "A07") (pinfunction "D2_A07") (pintype "passive"))
      (node (ref "ISA2") (pin "A07") (pinfunction "D2_A07") (pintype "passive"))
      (node (ref "ISA3") (pin "A07") (pinfunction "D2_A07") (pintype "passive"))
    )
    (net (code "68") (name "/ISA_D3") (class "Default")
      (node (ref "I1") (pin "A24") (pinfunction "A24_A24") (pintype "passive"))
      (node (ref "ISA1") (pin "A06") (pinfunction "D3_A06") (pintype "passive"))
      (node (ref "ISA2") (pin "A06") (pinfunction "D3_A06") (pintype "passive"))
      (node (ref "ISA3") (pin "A06") (pinfunction "D3_A06") (pintype "passive"))
    )
    (net (code "69") (name "/ISA_D4") (class "Default")
      (node (ref "I1") (pin "A28") (pinfunction "A28_A28") (pintype "passive"))
      (node (ref "ISA1") (pin "A05") (pinfunction "D4_A05") (pintype "passive"))
      (node (ref "ISA2") (pin "A05") (pinfunction "D4_A05") (pintype "passive"))
      (node (ref "ISA3") (pin "A05") (pinfunction "D4_A05") (pintype "passive"))
    )
    (net (code "70") (name "/ISA_D5") (class "Default")
      (node (ref "I1") (pin "A25") (pinfunction "A25_A25") (pintype "passive"))
      (node (ref "ISA1") (pin "A04") (pinfunction "D5_A04") (pintype "passive"))
      (node (ref "ISA2") (pin "A04") (pinfunction "D5_A04") (pintype "passive"))
      (node (ref "ISA3") (pin "A04") (pinfunction "D5_A04") (pintype "passive"))
    )
    (net (code "71") (name "/ISA_D6") (class "Default")
      (node (ref "I1") (pin "A27") (pinfunction "A27_A27") (pintype "passive"))
      (node (ref "ISA1") (pin "A03") (pinfunction "D6_A03") (pintype "passive"))
      (node (ref "ISA2") (pin "A03") (pinfunction "D6_A03") (pintype "passive"))
      (node (ref "ISA3") (pin "A03") (pinfunction "D6_A03") (pintype "passive"))
    )
    (net (code "72") (name "/ISA_D7") (class "Default")
      (node (ref "I1") (pin "A26") (pinfunction "A26_A26") (pintype "passive"))
      (node (ref "ISA1") (pin "A02") (pinfunction "D7_A02") (pintype "passive"))
      (node (ref "ISA2") (pin "A02") (pinfunction "D7_A02") (pintype "passive"))
      (node (ref "ISA3") (pin "A02") (pinfunction "D7_A02") (pintype "passive"))
    )
    (net (code "73") (name "/ISA_D8") (class "Default")
      (node (ref "I1") (pin "45") (pinfunction "45_45") (pintype "passive"))
      (node (ref "ISA1") (pin "C11") (pinfunction "D8_C11") (pintype "passive"))
      (node (ref "ISA2") (pin "C11") (pinfunction "D8_C11") (pintype "passive"))
      (node (ref "ISA3") (pin "C11") (pinfunction "D8_C11") (pintype "passive"))
    )
    (net (code "74") (name "/ISA_D9") (class "Default")
      (node (ref "I1") (pin "7") (pinfunction "7_7") (pintype "passive"))
      (node (ref "ISA1") (pin "C12") (pinfunction "D9_C12") (pintype "passive"))
      (node (ref "ISA2") (pin "C12") (pinfunction "D9_C12") (pintype "passive"))
      (node (ref "ISA3") (pin "C12") (pinfunction "D9_C12") (pintype "passive"))
    )
    (net (code "75") (name "/ISA_D10") (class "Default")
      (node (ref "I1") (pin "48") (pinfunction "48_48") (pintype "passive"))
      (node (ref "ISA1") (pin "C13") (pinfunction "D10_C13") (pintype "passive"))
      (node (ref "ISA2") (pin "C13") (pinfunction "D10_C13") (pintype "passive"))
      (node (ref "ISA3") (pin "C13") (pinfunction "D10_C13") (pintype "passive"))
    )
    (net (code "76") (name "/ISA_D11") (class "Default")
      (node (ref "I1") (pin "4") (pinfunction "4_4") (pintype "passive"))
      (node (ref "ISA1") (pin "C14") (pinfunction "D11_C14") (pintype "passive"))
      (node (ref "ISA2") (pin "C14") (pinfunction "D11_C14") (pintype "passive"))
      (node (ref "ISA3") (pin "C14") (pinfunction "D11_C14") (pintype "passive"))
    )
    (net (code "77") (name "/ISA_D12") (class "Default")
      (node (ref "I1") (pin "49") (pinfunction "49_49") (pintype "passive"))
      (node (ref "ISA1") (pin "C15") (pinfunction "D12_C15") (pintype "passive"))
      (node (ref "ISA2") (pin "C15") (pinfunction "D12_C15") (pintype "passive"))
      (node (ref "ISA3") (pin "C15") (pinfunction "D12_C15") (pintype "passive"))
    )
    (net (code "78") (name "/ISA_D13") (class "Default")
      (node (ref "I1") (pin "2") (pinfunction "2_2") (pintype "passive"))
      (node (ref "ISA1") (pin "C16") (pinfunction "D13_C16") (pintype "passive"))
      (node (ref "ISA2") (pin "C16") (pinfunction "D13_C16") (pintype "passive"))
      (node (ref "ISA3") (pin "C16") (pinfunction "D13_C16") (pintype "passive"))
    )
    (net (code "79") (name "/ISA_D14") (class "Default")
      (node (ref "I1") (pin "51") (pinfunction "51_51") (pintype "passive"))
      (node (ref "ISA1") (pin "C17") (pinfunction "D14_C17") (pintype "passive"))
      (node (ref "ISA2") (pin "C17") (pinfunction "D14_C17") (pintype "passive"))
      (node (ref "ISA3") (pin "C17") (pinfunction "D14_C17") (pintype "passive"))
    )
    (net (code "80") (name "/ISA_D15") (class "Default")
      (node (ref "I1") (pin "1") (pinfunction "1_1") (pintype "passive"))
      (node (ref "ISA1") (pin "C18") (pinfunction "D15_C18") (pintype "passive"))
      (node (ref "ISA2") (pin "C18") (pinfunction "D15_C18") (pintype "passive"))
      (node (ref "ISA3") (pin "C18") (pinfunction "D15_C18") (pintype "passive"))
    )
    (net (code "81") (name "/ISA_DRQ1") (class "Default")
      (node (ref "I1") (pin "A36") (pinfunction "A36_A36") (pintype "passive"))
      (node (ref "ISA1") (pin "B18") (pinfunction "DRQ1_B18") (pintype "passive"))
      (node (ref "ISA2") (pin "B18") (pinfunction "DRQ1_B18") (pintype "passive"))
      (node (ref "ISA3") (pin "B18") (pinfunction "DRQ1_B18") (pintype "passive"))
    )
    (net (code "82") (name "/ISA_DRQ2") (class "Default")
      (node (ref "I1") (pin "A13") (pinfunction "A13_A13") (pintype "passive"))
      (node (ref "ISA1") (pin "B06") (pinfunction "DRQ2_B06") (pintype "passive"))
      (node (ref "ISA2") (pin "B06") (pinfunction "DRQ2_B06") (pintype "passive"))
      (node (ref "ISA3") (pin "B06") (pinfunction "DRQ2_B06") (pintype "passive"))
    )
    (net (code "83") (name "/ISA_DRQ3") (class "Default")
      (node (ref "I1") (pin "A39") (pinfunction "A39_A39") (pintype "passive"))
      (node (ref "ISA1") (pin "B16") (pinfunction "DRQ3_B16") (pintype "passive"))
      (node (ref "ISA2") (pin "B16") (pinfunction "DRQ3_B16") (pintype "passive"))
      (node (ref "ISA3") (pin "B16") (pinfunction "DRQ3_B16") (pintype "passive"))
    )
    (net (code "84") (name "/ISA_IOREADY") (class "Default")
      (node (ref "I1") (pin "A45") (pinfunction "A45_A45") (pintype "passive"))
      (node (ref "ISA1") (pin "A10") (pinfunction "I/O_CH_RDY_A10") (pintype "passive"))
      (node (ref "ISA2") (pin "A10") (pinfunction "I/O_CH_RDY_A10") (pintype "passive"))
      (node (ref "ISA3") (pin "A10") (pinfunction "I/O_CH_RDY_A10") (pintype "passive"))
    )
    (net (code "85") (name "/ISA_IRQ2") (class "Default")
      (node (ref "I1") (pin "A4") (pinfunction "A4_A4") (pintype "passive"))
      (node (ref "ISA1") (pin "B04") (pinfunction "IRQ2_B04") (pintype "passive"))
      (node (ref "ISA2") (pin "B04") (pinfunction "IRQ2_B04") (pintype "passive"))
      (node (ref "ISA3") (pin "B04") (pinfunction "IRQ2_B04") (pintype "passive"))
    )
    (net (code "86") (name "/ISA_IRQ3") (class "Default")
      (node (ref "I1") (pin "A1") (pinfunction "A1_A1") (pintype "passive"))
      (node (ref "ISA1") (pin "B25") (pinfunction "IRQ3_B25") (pintype "passive"))
      (node (ref "ISA2") (pin "B25") (pinfunction "IRQ3_B25") (pintype "passive"))
      (node (ref "ISA3") (pin "B25") (pinfunction "IRQ3_B25") (pintype "passive"))
    )
    (net (code "87") (name "/ISA_IRQ4") (class "Default")
      (node (ref "I1") (pin "A51") (pinfunction "A51_A51") (pintype "passive"))
      (node (ref "ISA1") (pin "B24") (pinfunction "IRQ4_B24") (pintype "passive"))
      (node (ref "ISA2") (pin "B24") (pinfunction "IRQ4_B24") (pintype "passive"))
      (node (ref "ISA3") (pin "B24") (pinfunction "IRQ4_B24") (pintype "passive"))
    )
    (net (code "88") (name "/ISA_IRQ5") (class "Default")
      (node (ref "I1") (pin "A2") (pinfunction "A2_A2") (pintype "passive"))
      (node (ref "ISA1") (pin "B23") (pinfunction "IRQ5_B23") (pintype "passive"))
      (node (ref "ISA2") (pin "B23") (pinfunction "IRQ5_B23") (pintype "passive"))
      (node (ref "ISA3") (pin "B23") (pinfunction "IRQ5_B23") (pintype "passive"))
    )
    (net (code "89") (name "/ISA_IRQ6") (class "Default")
      (node (ref "I1") (pin "A5") (pinfunction "A5_A5") (pintype "passive"))
      (node (ref "ISA1") (pin "B22") (pinfunction "IRQ6_B22") (pintype "passive"))
      (node (ref "ISA2") (pin "B22") (pinfunction "IRQ6_B22") (pintype "passive"))
      (node (ref "ISA3") (pin "B22") (pinfunction "IRQ6_B22") (pintype "passive"))
    )
    (net (code "90") (name "/ISA_IRQ7") (class "Default")
      (node (ref "I1") (pin "A48") (pinfunction "A48_A48") (pintype "passive"))
      (node (ref "ISA1") (pin "B21") (pinfunction "IRQ7_B21") (pintype "passive"))
      (node (ref "ISA2") (pin "B21") (pinfunction "IRQ7_B21") (pintype "passive"))
      (node (ref "ISA3") (pin "B21") (pinfunction "IRQ7_B21") (pintype "passive"))
    )
    (net (code "91") (name "/ISA_OSC") (class "Default")
      (node (ref "I1") (pin "A16") (pinfunction "A16_A16") (pintype "passive"))
      (node (ref "ISA1") (pin "B30") (pinfunction "OSC_B30") (pintype "passive"))
      (node (ref "ISA2") (pin "B30") (pinfunction "OSC_B30") (pintype "passive"))
      (node (ref "ISA3") (pin "B30") (pinfunction "OSC_B30") (pintype "passive"))
    )
    (net (code "92") (name "/ISA_RESET") (class "Default")
      (node (ref "I1") (pin "A44") (pinfunction "A44_A44") (pintype "passive"))
      (node (ref "ISA1") (pin "B02") (pinfunction "RESET_DRV_B02") (pintype "passive"))
      (node (ref "ISA2") (pin "B02") (pinfunction "RESET_DRV_B02") (pintype "passive"))
      (node (ref "ISA3") (pin "B02") (pinfunction "RESET_DRV_B02") (pintype "passive"))
    )
    (net (code "93") (name "/ISA_T{slash}C") (class "Default")
      (node (ref "I1") (pin "A8") (pinfunction "A8_A8") (pintype "passive"))
      (node (ref "ISA1") (pin "B27") (pinfunction "T/C_B27") (pintype "passive"))
      (node (ref "ISA2") (pin "B27") (pinfunction "T/C_B27") (pintype "passive"))
      (node (ref "ISA3") (pin "B27") (pinfunction "T/C_B27") (pintype "passive"))
    )
    (net (code "94") (name "/KEY_A") (class "Default")
      (node (ref "C2") (pin "1") (pinfunction "1_1") (pintype "passive"))
      (node (ref "I1") (pin "A9") (pinfunction "A9_A9") (pintype "passive"))
      (node (ref "JKB") (pin "2") (pinfunction "2_2") (pintype "passive"))
      (node (ref "R4") (pin "1") (pinfunction "1_1") (pintype "passive"))
    )
    (net (code "95") (name "/KEY_B") (class "Default")
      (node (ref "C1") (pin "1") (pinfunction "1_1") (pintype "passive"))
      (node (ref "I1") (pin "A43") (pinfunction "A43_A43") (pintype "passive"))
      (node (ref "JKB") (pin "3") (pinfunction "3_3") (pintype "passive"))
      (node (ref "R7") (pin "1") (pinfunction "1_1") (pintype "passive"))
    )
    (net (code "96") (name "/VCC_CPU") (class "Default")
      (node (ref "I1") (pin "B13") (pinfunction "B13_B13") (pintype "passive"))
      (node (ref "I1") (pin "B14") (pinfunction "B14_B14") (pintype "passive"))
      (node (ref "I1") (pin "B15") (pinfunction "B15_B15") (pintype "passive"))
      (node (ref "J1") (pin "1") (pinfunction "1_1") (pintype "passive"))
    )
    (net (code "97") (name "GND") (class "Default")
      (node (ref "C1") (pin "2") (pinfunction "2_2") (pintype "passive"))
      (node (ref "C10") (pin "2") (pinfunction "2_2") (pintype "passive"))
      (node (ref "C11") (pin "2") (pinfunction "2_2") (pintype "passive"))
      (node (ref "C12") (pin "2") (pinfunction "2_2") (pintype "passive"))
      (node (ref "C13") (pin "2") (pinfunction "2_2") (pintype "passive"))
      (node (ref "C14") (pin "2") (pinfunction "2_2") (pintype "passive"))
      (node (ref "C15") (pin "2") (pinfunction "2_2") (pintype "passive"))
      (node (ref "C16") (pin "2") (pinfunction "2_2") (pintype "passive"))
      (node (ref "C17") (pin "2") (pinfunction "2_2") (pintype "passive"))
      (node (ref "C18") (pin "2") (pinfunction "2_2") (pintype "passive"))
      (node (ref "C19") (pin "2") (pinfunction "2_2") (pintype "passive"))
      (node (ref "C2") (pin "2") (pinfunction "2_2") (pintype "passive"))
      (node (ref "C20") (pin "2") (pinfunction "2_2") (pintype "passive"))
      (node (ref "C21") (pin "2") (pinfunction "2_2") (pintype "passive"))
      (node (ref "C22") (pin "2") (pinfunction "2_2") (pintype "passive"))
      (node (ref "C23") (pin "2") (pinfunction "2_2") (pintype "passive"))
      (node (ref "C24") (pin "2") (pinfunction "2_2") (pintype "passive"))
      (node (ref "C26") (pin "2") (pinfunction "2_2") (pintype "passive"))
      (node (ref "C27") (pin "2") (pinfunction "2_2") (pintype "passive"))
      (node (ref "C28") (pin "2") (pinfunction "2_2") (pintype "passive"))
      (node (ref "C5") (pin "2") (pinfunction "E_2") (pintype "passive"))
      (node (ref "C6") (pin "2") (pinfunction "2_2") (pintype "passive"))
      (node (ref "C7") (pin "2") (pinfunction "2_2") (pintype "passive"))
      (node (ref "C8") (pin "2") (pinfunction "2_2") (pintype "passive"))
      (node (ref "C9") (pin "2") (pinfunction "2_2") (pintype "passive"))
      (node (ref "I1") (pin "0") (pinfunction "0_0") (pintype "passive"))
      (node (ref "I1") (pin "11") (pinfunction "11_11") (pintype "passive"))
      (node (ref "I1") (pin "3") (pinfunction "3_3") (pintype "passive"))
      (node (ref "I1") (pin "39") (pinfunction "39_39") (pintype "passive"))
      (node (ref "I1") (pin "42") (pinfunction "42_42") (pintype "passive"))
      (node (ref "I1") (pin "50") (pinfunction "50_50") (pintype "passive"))
      (node (ref "I1") (pin "A22") (pinfunction "A22_A22") (pintype "passive"))
      (node (ref "I1") (pin "A46") (pinfunction "A46_A46") (pintype "passive"))
      (node (ref "I1") (pin "A7") (pinfunction "A7_A7") (pintype "passive"))
      (node (ref "I1") (pin "B1") (pinfunction "B1_B1") (pintype "passive"))
      (node (ref "I1") (pin "B2") (pinfunction "B2_B2") (pintype "passive"))
      (node (ref "I1") (pin "B3") (pinfunction "B3_B3") (pintype "passive"))
      (node (ref "I1") (pin "B4") (pinfunction "B4_B4") (pintype "passive"))
      (node (ref "I1") (pin "B5") (pinfunction "B5_B5") (pintype "passive"))
      (node (ref "I1") (pin "B6") (pinfunction "B6_B6") (pintype "passive"))
      (node (ref "I1") (pin "B7") (pinfunction "B7_B7") (pintype "passive"))
      (node (ref "I1") (pin "B8") (pinfunction "B8_B8") (pintype "passive"))
      (node (ref "ISA1") (pin "B01") (pinfunction "GND_B01") (pintype "passive"))
      (node (ref "ISA1") (pin "B10") (pinfunction "GND_B10") (pintype "passive"))
      (node (ref "ISA1") (pin "B31") (pinfunction "GND_B31") (pintype "passive"))
      (node (ref "ISA1") (pin "D18") (pinfunction "GND_D18") (pintype "passive"))
      (node (ref "ISA2") (pin "B01") (pinfunction "GND_B01") (pintype "passive"))
      (node (ref "ISA2") (pin "B10") (pinfunction "GND_B10") (pintype "passive"))
      (node (ref "ISA2") (pin "B31") (pinfunction "GND_B31") (pintype "passive"))
      (node (ref "ISA2") (pin "D18") (pinfunction "GND_D18") (pintype "passive"))
      (node (ref "ISA3") (pin "B01") (pinfunction "GND_B01") (pintype "passive"))
      (node (ref "ISA3") (pin "B10") (pinfunction "GND_B10") (pintype "passive"))
      (node (ref "ISA3") (pin "B31") (pinfunction "GND_B31") (pintype "passive"))
      (node (ref "ISA3") (pin "D18") (pinfunction "GND_D18") (pintype "passive"))
      (node (ref "J10") (pin "2") (pinfunction "2_2") (pintype "passive"))
      (node (ref "J11") (pin "2") (pinfunction "2_2") (pintype "passive"))
      (node (ref "J5") (pin "2") (pinfunction "-_2") (pintype "passive"))
      (node (ref "J5") (pin "3") (pinfunction "-_3") (pintype "passive"))
      (node (ref "J8") (pin "2") (pinfunction "2_2") (pintype "passive"))
      (node (ref "J9") (pin "2") (pinfunction "2_2") (pintype "passive"))
      (node (ref "JKB") (pin "4") (pinfunction "4_4") (pintype "passive"))
      (node (ref "Jbat") (pin "2") (pinfunction "2_2") (pintype "passive"))
      (node (ref "LED1") (pin "2") (pintype "passive"))
      (node (ref "M2") (pin "1") (pinfunction "1_1") (pintype "passive"))
      (node (ref "M3") (pin "1") (pinfunction "1_1") (pintype "passive"))
      (node (ref "M4") (pin "1") (pinfunction "1_1") (pintype "passive"))
      (node (ref "M5") (pin "1") (pinfunction "1_1") (pintype "passive"))
    )
    (net (code "98") (name "Net-(LED1-Pad1)") (class "Default")
      (node (ref "LED1") (pin "1") (pintype "passive"))
      (node (ref "R3") (pin "1") (pinfunction "1_1") (pintype "passive"))
    )
    (net (code "99") (name "VCC") (class "Default")
      (node (ref "C10") (pin "1") (pinfunction "1_1") (pintype "passive"))
      (node (ref "C11") (pin "1") (pinfunction "1_1") (pintype "passive"))
      (node (ref "C12") (pin "1") (pinfunction "1_1") (pintype "passive"))
      (node (ref "C13") (pin "1") (pinfunction "1_1") (pintype "passive"))
      (node (ref "C14") (pin "1") (pinfunction "1_1") (pintype "passive"))
      (node (ref "C15") (pin "1") (pinfunction "1_1") (pintype "passive"))
      (node (ref "C16") (pin "1") (pinfunction "1_1") (pintype "passive"))
      (node (ref "C17") (pin "1") (pinfunction "1_1") (pintype "passive"))
      (node (ref "C18") (pin "1") (pinfunction "1_1") (pintype "passive"))
      (node (ref "C19") (pin "1") (pinfunction "1_1") (pintype "passive"))
      (node (ref "C20") (pin "1") (pinfunction "1_1") (pintype "passive"))
      (node (ref "C21") (pin "1") (pinfunction "1_1") (pintype "passive"))
      (node (ref "C22") (pin "1") (pinfunction "1_1") (pintype "passive"))
      (node (ref "C23") (pin "1") (pinfunction "1_1") (pintype "passive"))
      (node (ref "C24") (pin "1") (pinfunction "1_1") (pintype "passive"))
      (node (ref "C26") (pin "1") (pinfunction "1_1") (pintype "passive"))
      (node (ref "C27") (pin "1") (pinfunction "1_1") (pintype "passive"))
      (node (ref "C28") (pin "1") (pinfunction "1_1") (pintype "passive"))
      (node (ref "C6") (pin "1") (pinfunction "1_1") (pintype "passive"))
      (node (ref "C7") (pin "1") (pinfunction "1_1") (pintype "passive"))
      (node (ref "C8") (pin "1") (pinfunction "1_1") (pintype "passive"))
      (node (ref "C9") (pin "1") (pinfunction "1_1") (pintype "passive"))
      (node (ref "I1") (pin "B10") (pinfunction "B10_B10") (pintype "passive"))
      (node (ref "I1") (pin "B11") (pinfunction "B11_B11") (pintype "passive"))
      (node (ref "I1") (pin "B12") (pinfunction "B12_B12") (pintype "passive"))
      (node (ref "I1") (pin "B9") (pinfunction "B9_B9") (pintype "passive"))
      (node (ref "ISA1") (pin "B03") (pinfunction "+5V_B03") (pintype "passive"))
      (node (ref "ISA1") (pin "B29") (pinfunction "+5V_B29") (pintype "passive"))
      (node (ref "ISA1") (pin "D16") (pinfunction "+5V_D16") (pintype "passive"))
      (node (ref "ISA2") (pin "B03") (pinfunction "+5V_B03") (pintype "passive"))
      (node (ref "ISA2") (pin "B29") (pinfunction "+5V_B29") (pintype "passive"))
      (node (ref "ISA2") (pin "D16") (pinfunction "+5V_D16") (pintype "passive"))
      (node (ref "ISA3") (pin "B03") (pinfunction "+5V_B03") (pintype "passive"))
      (node (ref "ISA3") (pin "B29") (pinfunction "+5V_B29") (pintype "passive"))
      (node (ref "ISA3") (pin "D16") (pinfunction "+5V_D16") (pintype "passive"))
      (node (ref "J1") (pin "2") (pinfunction "2_2") (pintype "passive"))
      (node (ref "J10") (pin "1") (pinfunction "1_1") (pintype "passive"))
      (node (ref "J11") (pin "1") (pinfunction "1_1") (pintype "passive"))
      (node (ref "J8") (pin "1") (pinfunction "1_1") (pintype "passive"))
      (node (ref "J9") (pin "1") (pinfunction "1_1") (pintype "passive"))
      (node (ref "JKB") (pin "1") (pinfunction "1_1") (pintype "passive"))
      (node (ref "R3") (pin "2") (pinfunction "2_2") (pintype "passive"))
      (node (ref "R4") (pin "2") (pinfunction "2_2") (pintype "passive"))
      (node (ref "R7") (pin "2") (pinfunction "2_2") (pintype "passive"))
      (node (ref "S1") (pin "2") (pinfunction "NC1_2") (pintype "passive"))
      (node (ref "S1") (pin "5") (pinfunction "COMMON2_5") (pintype "passive"))
    )
    (net (code "100") (name "unconnected-(I1-Pad34)") (class "Default")
      (node (ref "I1") (pin "34") (pinfunction "34_34") (pintype "passive"))
    )
    (net (code "101") (name "unconnected-(I1-Pad36)") (class "Default")
      (node (ref "I1") (pin "36") (pinfunction "36_36") (pintype "passive"))
    )
    (net (code "102") (name "unconnected-(I1-Pad38)") (class "Default")
      (node (ref "I1") (pin "38") (pinfunction "38_38") (pintype "passive"))
    )
    (net (code "103") (name "unconnected-(S1-NC2-Pad4)") (class "Default")
      (node (ref "S1") (pin "4") (pinfunction "NC2_4") (pintype "passive"))
    )
    (net (code "104") (name "unconnected-(S1-NO1-Pad1)") (class "Default")
      (node (ref "S1") (pin "1") (pinfunction "NO1_1") (pintype "passive"))
    )
  )
)
